# sensors.net
KiCad netlist of a schematic drawn in Altium Designer
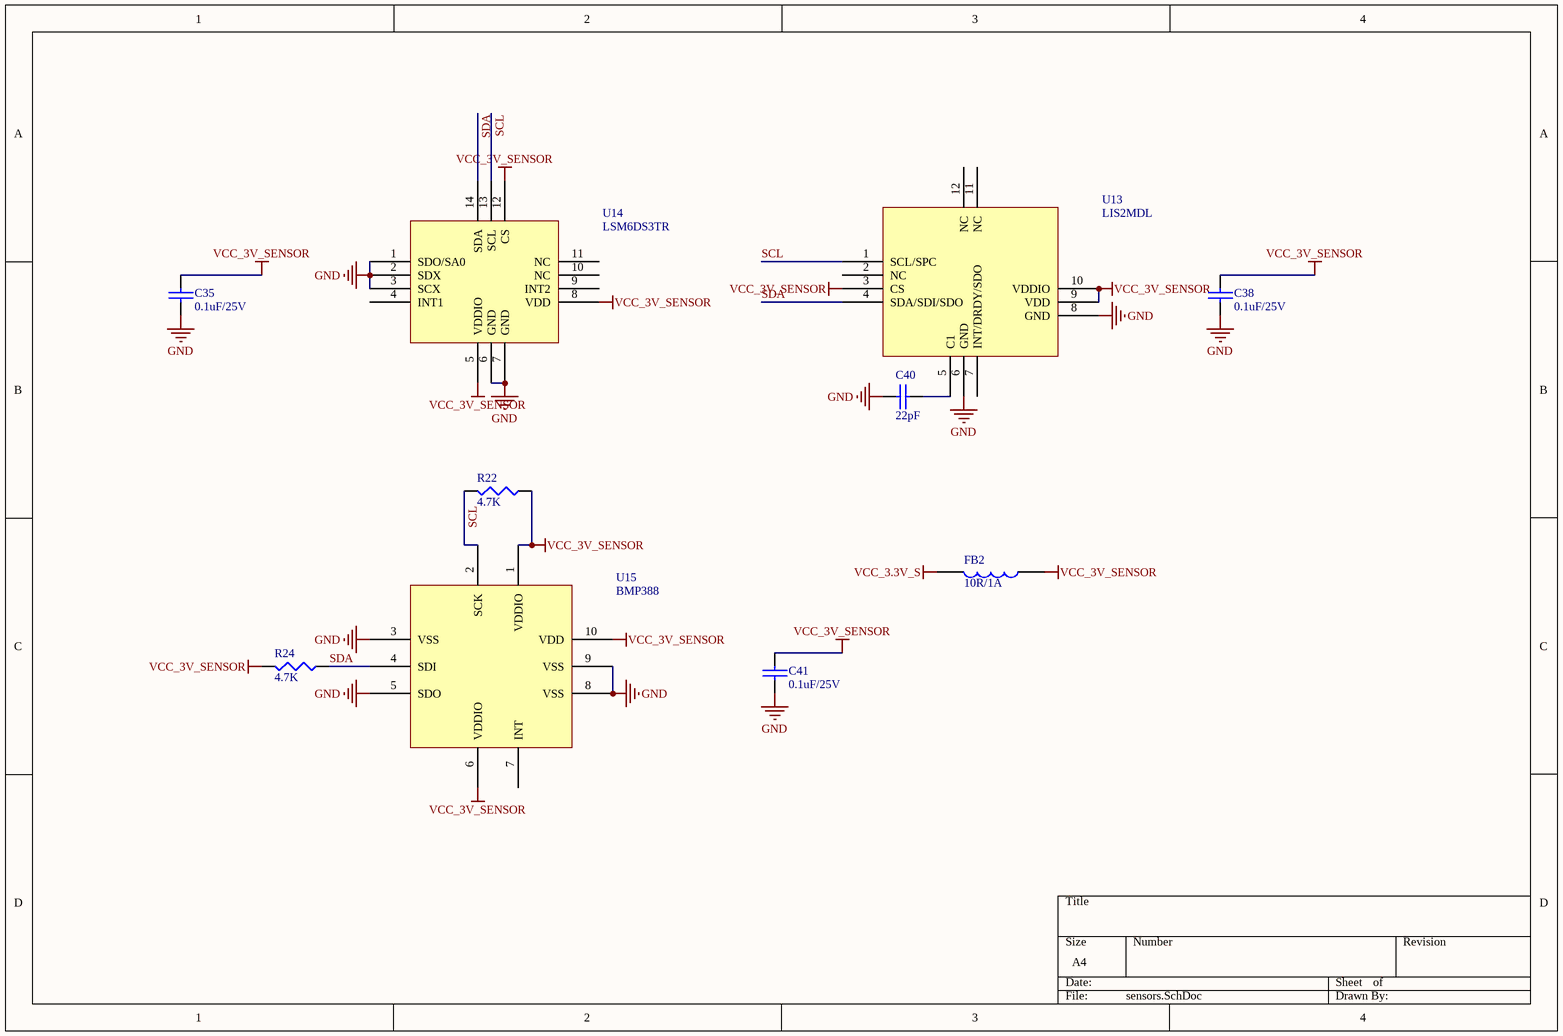
[diagram p0: sensors.SchDoc]

(export (version "E")
  (design (tool "Eeschema 10.0.6"))
  (components
    (comp (ref "C35")
      (value "0.1uF/25V")
      (footprint "0402C")
      (description "Capacitor")
      (libsource (lib "ZWLIntegrated_Library") (part "CAP"))
    )
    (comp (ref "C38")
      (value "0.1uF/25V")
      (footprint "0402C")
      (description "Capacitor")
      (libsource (lib "ZWLIntegrated_Library") (part "CAP"))
    )
    (comp (ref "C40")
      (value "22pF")
      (footprint "0402c")
      (description "Capacitor")
      (libsource (lib "SM") (part "CAP"))
    )
    (comp (ref "C41")
      (value "0.1uF/25V")
      (footprint "0402C")
      (description "Capacitor")
      (libsource (lib "ZWLIntegrated_Library") (part "CAP"))
    )
    (comp (ref "FB2") (value "10R/1A") (footprint "0603R") (libsource (lib "*") (part "INDUCTOR1")))
    (comp (ref "R22")
      (value "4.7K")
      (footprint "0402R")
      (libsource (lib "ZWLIntegrated_Library") (part "RES1"))
    )
    (comp (ref "R24")
      (value "4.7K")
      (footprint "0402R")
      (libsource (lib "ZWLIntegrated_Library") (part "RES1"))
    )
    (comp (ref "U13") (value "LIS2MDL") (footprint "LIS2MDL") (libsource (lib "stm32") (part "LIS2MDL")))
    (comp (ref "U14")
      (value "LSM6DS3TR")
      (footprint "LSM6DS3TR-C")
      (libsource (lib "stm32") (part "LSM6DS3TR"))
    )
    (comp (ref "U15") (value "BMP388") (footprint "BMP388") (libsource (lib "stm32") (part "BMP388")))
  )
  (nets
    (net (code "1") (name "/SCL") (class "Default")
      (node (ref "R22") (pin "2") (pinfunction "2_2") (pintype "passive"))
      (node (ref "U13") (pin "1") (pinfunction "SCL/SPC_1") (pintype "passive"))
      (node (ref "U14") (pin "13") (pinfunction "SCL_13") (pintype "passive"))
      (node (ref "U15") (pin "2") (pinfunction "SCK_2") (pintype "passive"))
    )
    (net (code "2") (name "/SDA") (class "Default")
      (node (ref "R24") (pin "1") (pinfunction "1_1") (pintype "passive"))
      (node (ref "U13") (pin "4") (pinfunction "SDA/SDI/SDO_4") (pintype "passive"))
      (node (ref "U14") (pin "14") (pinfunction "SDA_14") (pintype "passive"))
      (node (ref "U15") (pin "4") (pinfunction "SDI_4") (pintype "passive"))
    )
    (net (code "3") (name "GND") (class "Default")
      (node (ref "C35") (pin "1") (pinfunction "1_1") (pintype "passive"))
      (node (ref "C38") (pin "1") (pinfunction "1_1") (pintype "passive"))
      (node (ref "C40") (pin "2") (pinfunction "2_2") (pintype "passive"))
      (node (ref "C41") (pin "1") (pinfunction "1_1") (pintype "passive"))
      (node (ref "U13") (pin "6") (pinfunction "GND_6") (pintype "passive"))
      (node (ref "U13") (pin "8") (pinfunction "GND_8") (pintype "passive"))
      (node (ref "U14") (pin "1") (pinfunction "SDO/SA0_1") (pintype "passive"))
      (node (ref "U14") (pin "2") (pinfunction "SDX_2") (pintype "passive"))
      (node (ref "U14") (pin "3") (pinfunction "SCX_3") (pintype "passive"))
      (node (ref "U14") (pin "6") (pinfunction "GND_6") (pintype "passive"))
      (node (ref "U14") (pin "7") (pinfunction "GND_7") (pintype "passive"))
      (node (ref "U15") (pin "3") (pinfunction "VSS_3") (pintype "passive"))
      (node (ref "U15") (pin "5") (pinfunction "SDO_5") (pintype "passive"))
      (node (ref "U15") (pin "8") (pinfunction "VSS_8") (pintype "passive"))
      (node (ref "U15") (pin "9") (pinfunction "VSS_9") (pintype "passive"))
    )
    (net (code "4") (name "Net-(U13-C1)") (class "Default")
      (node (ref "C40") (pin "1") (pinfunction "1_1") (pintype "passive"))
      (node (ref "U13") (pin "5") (pinfunction "C1_5") (pintype "passive"))
    )
    (net (code "5") (name "VCC_3.3V_S") (class "Default")
      (node (ref "FB2") (pin "1") (pinfunction "1_1") (pintype "passive"))
    )
    (net (code "6") (name "VCC_3V_SENSOR") (class "Default")
      (node (ref "C35") (pin "2") (pinfunction "2_2") (pintype "passive"))
      (node (ref "C38") (pin "2") (pinfunction "2_2") (pintype "passive"))
      (node (ref "C41") (pin "2") (pinfunction "2_2") (pintype "passive"))
      (node (ref "FB2") (pin "2") (pinfunction "2_2") (pintype "passive"))
      (node (ref "R22") (pin "1") (pinfunction "1_1") (pintype "passive"))
      (node (ref "R24") (pin "2") (pinfunction "2_2") (pintype "passive"))
      (node (ref "U13") (pin "10") (pinfunction "VDDIO_10") (pintype "passive"))
      (node (ref "U13") (pin "3") (pinfunction "CS_3") (pintype "passive"))
      (node (ref "U13") (pin "9") (pinfunction "VDD_9") (pintype "passive"))
      (node (ref "U14") (pin "12") (pinfunction "CS_12") (pintype "passive"))
      (node (ref "U14") (pin "5") (pinfunction "VDDIO_5") (pintype "passive"))
      (node (ref "U14") (pin "8") (pinfunction "VDD_8") (pintype "passive"))
      (node (ref "U15") (pin "1") (pinfunction "VDDIO_1") (pintype "passive"))
      (node (ref "U15") (pin "10") (pinfunction "VDD_10") (pintype "passive"))
      (node (ref "U15") (pin "6") (pinfunction "VDDIO_6") (pintype "passive"))
    )
    (net (code "7") (name "unconnected-(U13-INT{slash}DRDY{slash}SDO-Pad7)") (class "Default")
      (node (ref "U13") (pin "7") (pinfunction "INT/DRDY/SDO_7") (pintype "passive"))
    )
    (net (code "8") (name "unconnected-(U13-NC-Pad2)") (class "Default")
      (node (ref "U13") (pin "2") (pinfunction "NC_2") (pintype "passive"))
    )
    (net (code "9") (name "unconnected-(U13-NC-Pad11)") (class "Default")
      (node (ref "U13") (pin "11") (pinfunction "NC_11") (pintype "passive"))
    )
    (net (code "10") (name "unconnected-(U13-NC-Pad12)") (class "Default")
      (node (ref "U13") (pin "12") (pinfunction "NC_12") (pintype "passive"))
    )
    (net (code "11") (name "unconnected-(U14-INT1-Pad4)") (class "Default")
      (node (ref "U14") (pin "4") (pinfunction "INT1_4") (pintype "passive"))
    )
    (net (code "12") (name "unconnected-(U14-INT2-Pad9)") (class "Default")
      (node (ref "U14") (pin "9") (pinfunction "INT2_9") (pintype "passive"))
    )
    (net (code "13") (name "unconnected-(U14-NC-Pad10)") (class "Default")
      (node (ref "U14") (pin "10") (pinfunction "NC_10") (pintype "passive"))
    )
    (net (code "14") (name "unconnected-(U14-NC-Pad11)") (class "Default")
      (node (ref "U14") (pin "11") (pinfunction "NC_11") (pintype "passive"))
    )
    (net (code "15") (name "unconnected-(U15-INT-Pad7)") (class "Default")
      (node (ref "U15") (pin "7") (pinfunction "INT_7") (pintype "passive"))
    )
  )
)
